# LED2.net
KiCad netlist of a schematic drawn in Altium Designer
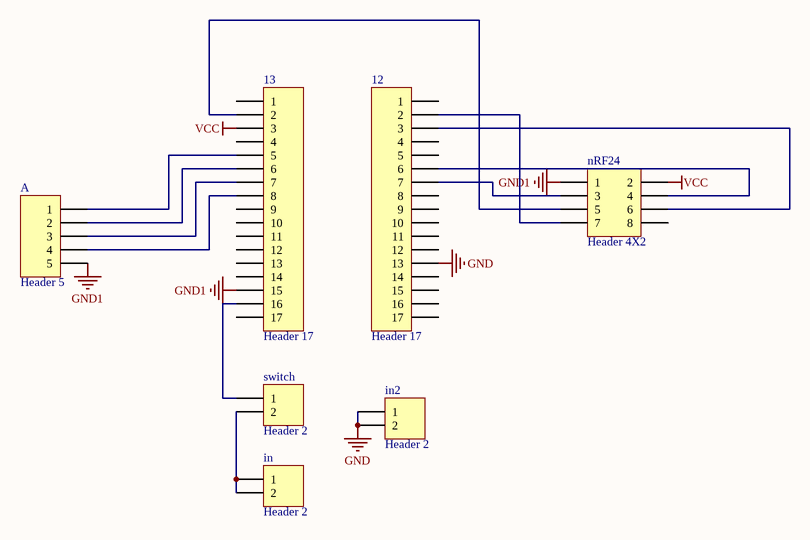
[diagram p0: LED2.SchDoc]

(export (version "E")
  (design (tool "Eeschema 10.0.6"))
  (components
    (comp (ref "12")
      (value "Header 17")
      (footprint "HDR1X17")
      (description "Header, 17-Pin")
      (fields (field (name "PUBLISHER") "Altium Limited"))
      (libsource (lib "Miscellaneous Connectors") (part "Header 17"))
    )
    (comp (ref "13")
      (value "Header 17")
      (footprint "HDR1X17")
      (description "Header, 17-Pin")
      (fields (field (name "PUBLISHER") "Altium Limited"))
      (libsource (lib "") (part "Header 17_1"))
    )
    (comp (ref "A")
      (value "Header 5")
      (footprint "HDR1X5")
      (description "Header, 5-Pin")
      (fields (field (name "PUBLISHER") "Altium Limited"))
      (libsource (lib "Miscellaneous Connectors") (part "Header 5"))
    )
    (comp (ref "in")
      (value "Header 2")
      (footprint "HDR1X2")
      (description "Header, 2-Pin")
      (fields (field (name "PUBLISHER") "Altium Limited"))
      (libsource (lib "Miscellaneous Connectors") (part "Header 2"))
    )
    (comp (ref "in2")
      (value "Header 2")
      (footprint "HDR1X2")
      (description "Header, 2-Pin")
      (fields (field (name "PUBLISHER") "Altium Limited"))
      (libsource (lib "Miscellaneous Connectors") (part "Header 2"))
    )
    (comp (ref "nRF24")
      (value "Header 4X2")
      (footprint "HDR2X4")
      (description "Header, 4-Pin, Dual row")
      (fields (field (name "PUBLISHER") "Altium Limited"))
      (libsource (lib "Miscellaneous Connectors") (part "Header 4X2"))
    )
    (comp (ref "switch")
      (value "Header 2")
      (footprint "HDR1X2")
      (description "Header, 2-Pin")
      (fields (field (name "PUBLISHER") "Altium Limited"))
      (libsource (lib "Miscellaneous Connectors") (part "Header 2"))
    )
  )
  (nets
    (net (code "1") (name "GND") (class "Default")
      (node (ref "12") (pin "13") (pinfunction "13_13") (pintype "passive"))
      (node (ref "in2") (pin "1") (pinfunction "1_1") (pintype "passive"))
      (node (ref "in2") (pin "2") (pinfunction "2_2") (pintype "passive"))
    )
    (net (code "2") (name "GND1") (class "Default")
      (node (ref "13") (pin "15") (pinfunction "15_15") (pintype "passive"))
      (node (ref "A") (pin "5") (pinfunction "5_5") (pintype "passive"))
      (node (ref "nRF24") (pin "1") (pinfunction "1_1") (pintype "passive"))
    )
    (net (code "3") (name "Net-(12-Pad2)") (class "Default")
      (node (ref "12") (pin "2") (pinfunction "2_2") (pintype "passive"))
      (node (ref "nRF24") (pin "7") (pinfunction "7_7") (pintype "passive"))
    )
    (net (code "4") (name "Net-(12-Pad3)") (class "Default")
      (node (ref "12") (pin "3") (pinfunction "3_3") (pintype "passive"))
      (node (ref "nRF24") (pin "6") (pinfunction "6_6") (pintype "passive"))
    )
    (net (code "5") (name "Net-(12-Pad6)") (class "Default")
      (node (ref "12") (pin "6") (pinfunction "6_6") (pintype "passive"))
      (node (ref "nRF24") (pin "4") (pinfunction "4_4") (pintype "passive"))
    )
    (net (code "6") (name "Net-(12-Pad7)") (class "Default")
      (node (ref "12") (pin "7") (pinfunction "7_7") (pintype "passive"))
      (node (ref "nRF24") (pin "3") (pinfunction "3_3") (pintype "passive"))
    )
    (net (code "7") (name "Net-(13-Pad2)") (class "Default")
      (node (ref "13") (pin "2") (pinfunction "2_2") (pintype "passive"))
      (node (ref "nRF24") (pin "5") (pinfunction "5_5") (pintype "passive"))
    )
    (net (code "8") (name "Net-(13-Pad5)") (class "Default")
      (node (ref "13") (pin "5") (pinfunction "5_5") (pintype "passive"))
      (node (ref "A") (pin "1") (pinfunction "1_1") (pintype "passive"))
    )
    (net (code "9") (name "Net-(13-Pad6)") (class "Default")
      (node (ref "13") (pin "6") (pinfunction "6_6") (pintype "passive"))
      (node (ref "A") (pin "2") (pinfunction "2_2") (pintype "passive"))
    )
    (net (code "10") (name "Net-(13-Pad7)") (class "Default")
      (node (ref "13") (pin "7") (pinfunction "7_7") (pintype "passive"))
      (node (ref "A") (pin "3") (pinfunction "3_3") (pintype "passive"))
    )
    (net (code "11") (name "Net-(13-Pad8)") (class "Default")
      (node (ref "13") (pin "8") (pinfunction "8_8") (pintype "passive"))
      (node (ref "A") (pin "4") (pinfunction "4_4") (pintype "passive"))
    )
    (net (code "12") (name "Net-(13-Pad16)") (class "Default")
      (node (ref "13") (pin "16") (pinfunction "16_16") (pintype "passive"))
      (node (ref "switch") (pin "1") (pinfunction "1_1") (pintype "passive"))
    )
    (net (code "13") (name "Net-(in-Pad1)") (class "Default")
      (node (ref "in") (pin "1") (pinfunction "1_1") (pintype "passive"))
      (node (ref "in") (pin "2") (pinfunction "2_2") (pintype "passive"))
      (node (ref "switch") (pin "2") (pinfunction "2_2") (pintype "passive"))
    )
    (net (code "14") (name "VCC") (class "Default")
      (node (ref "13") (pin "3") (pinfunction "3_3") (pintype "passive"))
      (node (ref "nRF24") (pin "2") (pinfunction "2_2") (pintype "passive"))
    )
    (net (code "15") (name "unconnected-(12-Pad1)") (class "Default")
      (node (ref "12") (pin "1") (pinfunction "1_1") (pintype "passive"))
    )
    (net (code "16") (name "unconnected-(12-Pad4)") (class "Default")
      (node (ref "12") (pin "4") (pinfunction "4_4") (pintype "passive"))
    )
    (net (code "17") (name "unconnected-(12-Pad5)") (class "Default")
      (node (ref "12") (pin "5") (pinfunction "5_5") (pintype "passive"))
    )
    (net (code "18") (name "unconnected-(12-Pad8)") (class "Default")
      (node (ref "12") (pin "8") (pinfunction "8_8") (pintype "passive"))
    )
    (net (code "19") (name "unconnected-(12-Pad9)") (class "Default")
      (node (ref "12") (pin "9") (pinfunction "9_9") (pintype "passive"))
    )
    (net (code "20") (name "unconnected-(12-Pad10)") (class "Default")
      (node (ref "12") (pin "10") (pinfunction "10_10") (pintype "passive"))
    )
    (net (code "21") (name "unconnected-(12-Pad11)") (class "Default")
      (node (ref "12") (pin "11") (pinfunction "11_11") (pintype "passive"))
    )
    (net (code "22") (name "unconnected-(12-Pad12)") (class "Default")
      (node (ref "12") (pin "12") (pinfunction "12_12") (pintype "passive"))
    )
    (net (code "23") (name "unconnected-(12-Pad14)") (class "Default")
      (node (ref "12") (pin "14") (pinfunction "14_14") (pintype "passive"))
    )
    (net (code "24") (name "unconnected-(12-Pad15)") (class "Default")
      (node (ref "12") (pin "15") (pinfunction "15_15") (pintype "passive"))
    )
    (net (code "25") (name "unconnected-(12-Pad16)") (class "Default")
      (node (ref "12") (pin "16") (pinfunction "16_16") (pintype "passive"))
    )
    (net (code "26") (name "unconnected-(12-Pad17)") (class "Default")
      (node (ref "12") (pin "17") (pinfunction "17_17") (pintype "passive"))
    )
    (net (code "27") (name "unconnected-(13-Pad1)") (class "Default")
      (node (ref "13") (pin "1") (pinfunction "1_1") (pintype "passive"))
    )
    (net (code "28") (name "unconnected-(13-Pad4)") (class "Default")
      (node (ref "13") (pin "4") (pinfunction "4_4") (pintype "passive"))
    )
    (net (code "29") (name "unconnected-(13-Pad9)") (class "Default")
      (node (ref "13") (pin "9") (pinfunction "9_9") (pintype "passive"))
    )
    (net (code "30") (name "unconnected-(13-Pad10)") (class "Default")
      (node (ref "13") (pin "10") (pinfunction "10_10") (pintype "passive"))
    )
    (net (code "31") (name "unconnected-(13-Pad11)") (class "Default")
      (node (ref "13") (pin "11") (pinfunction "11_11") (pintype "passive"))
    )
    (net (code "32") (name "unconnected-(13-Pad12)") (class "Default")
      (node (ref "13") (pin "12") (pinfunction "12_12") (pintype "passive"))
    )
    (net (code "33") (name "unconnected-(13-Pad13)") (class "Default")
      (node (ref "13") (pin "13") (pinfunction "13_13") (pintype "passive"))
    )
    (net (code "34") (name "unconnected-(13-Pad14)") (class "Default")
      (node (ref "13") (pin "14") (pinfunction "14_14") (pintype "passive"))
    )
    (net (code "35") (name "unconnected-(13-Pad17)") (class "Default")
      (node (ref "13") (pin "17") (pinfunction "17_17") (pintype "passive"))
    )
    (net (code "36") (name "unconnected-(nRF24-Pad8)") (class "Default")
      (node (ref "nRF24") (pin "8") (pinfunction "8_8") (pintype "passive"))
    )
  )
)
